# USB-C_Power_Supply.net
KiCad netlist of a schematic drawn in Altium Designer
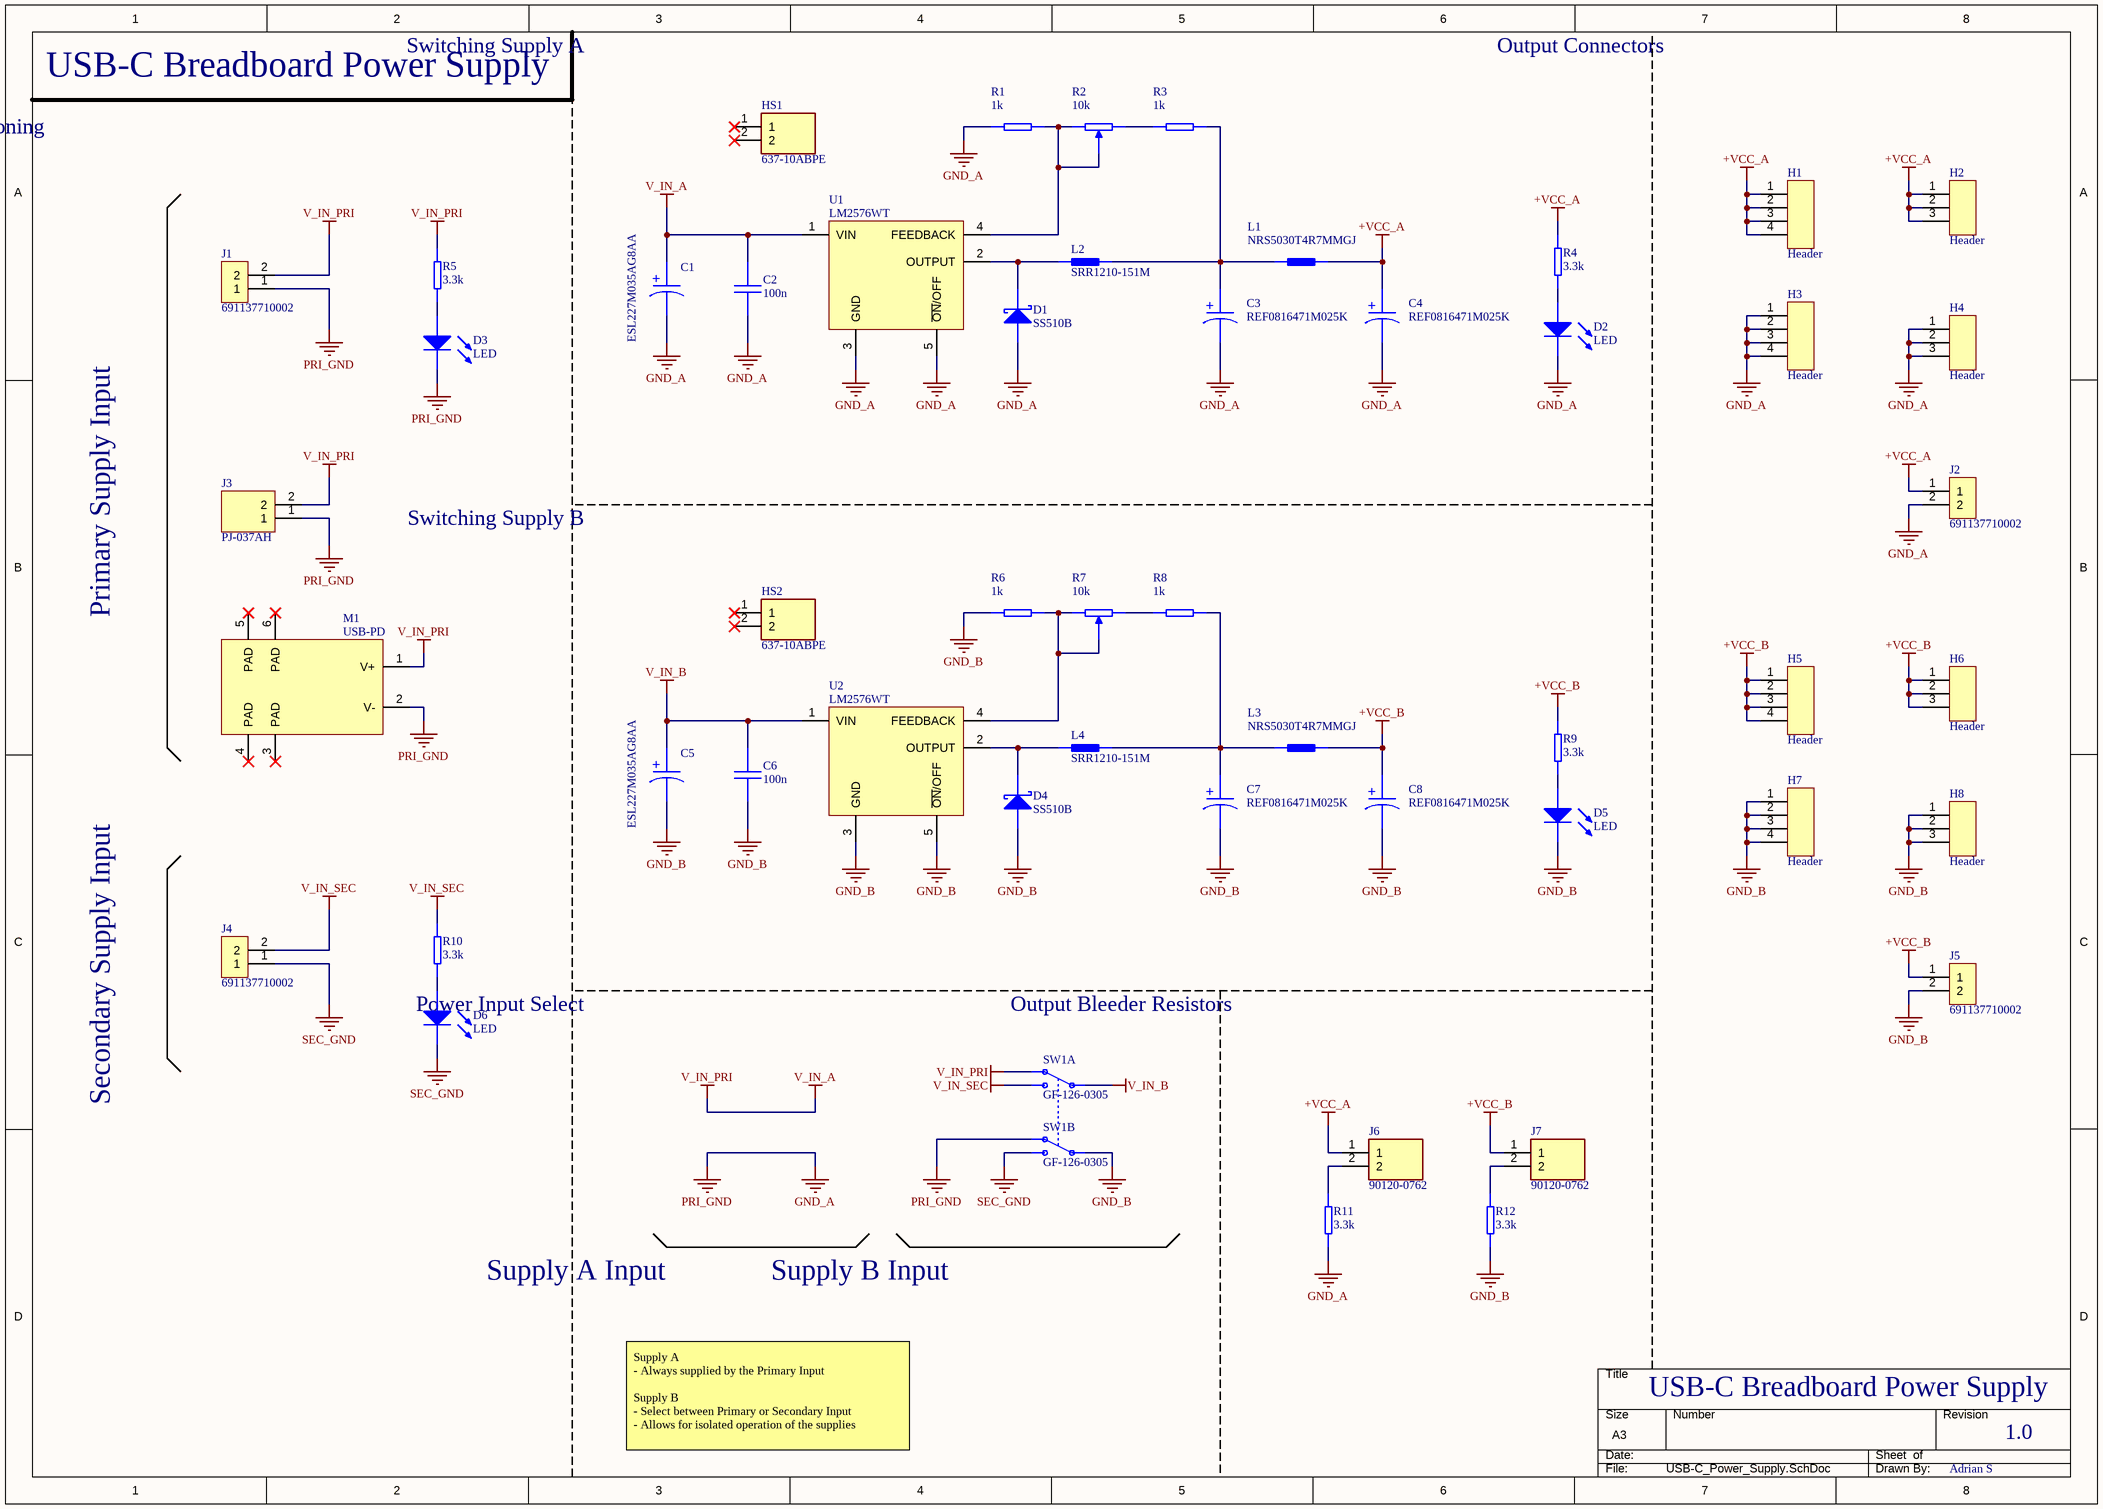
[diagram p0: USB-C_Power_Supply.SchDoc]

(export (version "E")
  (design (tool "Eeschema 10.0.6"))
  (components
    (comp (ref "C1")
      (value "ESL227M035AG8AA")
      (footprint "CAPTH8.00X18.00-3.50")
      (description "Capacitor Polarised")
      (fields (field (name "MOUSER PART NUMBER") "80-ESL227M035AG8AA"))
      (libsource (lib "TD") (part "ESL227M035AG8AA"))
    )
    (comp (ref "C2")
      (value "100n")
      (footprint "CAP0805")
      (description "Non Polarized Capacitor")
      (libsource (lib "TD") (part "Capacitor - Non Polarized"))
    )
    (comp (ref "C3")
      (value "REF0816471M025K")
      (footprint "CAPTH8.00X16.00-3.50")
      (description "Capacitor Polarised")
      (fields (field (name "MOUSER PART NUMBER") "581-REF0816471M025K"))
      (libsource (lib "TD") (part "REF0816471M025K"))
    )
    (comp (ref "C4")
      (value "REF0816471M025K")
      (footprint "CAPTH8.00X16.00-3.50")
      (description "Capacitor Polarised")
      (fields (field (name "MOUSER PART NUMBER") "581-REF0816471M025K"))
      (libsource (lib "TD") (part "REF0816471M025K"))
    )
    (comp (ref "C5")
      (value "ESL227M035AG8AA")
      (footprint "CAPTH8.00X18.00-3.50")
      (description "Capacitor Polarised")
      (fields (field (name "MOUSER PART NUMBER") "80-ESL227M035AG8AA"))
      (libsource (lib "TD") (part "ESL227M035AG8AA"))
    )
    (comp (ref "C6")
      (value "100n")
      (footprint "CAP0805")
      (description "Non Polarized Capacitor")
      (libsource (lib "TD") (part "Capacitor - Non Polarized"))
    )
    (comp (ref "C7")
      (value "REF0816471M025K")
      (footprint "CAPTH8.00X16.00-3.50")
      (description "Capacitor Polarised")
      (fields (field (name "MOUSER PART NUMBER") "581-REF0816471M025K"))
      (libsource (lib "TD") (part "REF0816471M025K"))
    )
    (comp (ref "C8")
      (value "REF0816471M025K")
      (footprint "CAPTH8.00X16.00-3.50")
      (description "Capacitor Polarised")
      (fields (field (name "MOUSER PART NUMBER") "581-REF0816471M025K"))
      (libsource (lib "TD") (part "REF0816471M025K"))
    )
    (comp (ref "D1")
      (value "SS510B")
      (footprint "DO-214AC (SMA)")
      (description "Diode")
      (libsource (lib "TD") (part "SS510B"))
    )
    (comp (ref "D2")
      (value "LED")
      (footprint "LEDM2012X80N")
      (description "General Purpose LED")
      (libsource (lib "TD") (part "LED"))
    )
    (comp (ref "D3")
      (value "LED")
      (footprint "LEDM2012X80N")
      (description "General Purpose LED")
      (libsource (lib "TD") (part "LED"))
    )
    (comp (ref "D4")
      (value "SS510B")
      (footprint "DO-214AC (SMA)")
      (description "Diode")
      (libsource (lib "TD") (part "SS510B"))
    )
    (comp (ref "D5")
      (value "LED")
      (footprint "LEDM2012X80N")
      (description "General Purpose LED")
      (libsource (lib "TD") (part "LED"))
    )
    (comp (ref "D6")
      (value "LED")
      (footprint "LEDM2012X80N")
      (description "General Purpose LED")
      (libsource (lib "TD") (part "LED"))
    )
    (comp (ref "H1")
      (value "Header")
      (footprint "Header_1X4")
      (description "4-Pin Header")
      (libsource (lib "TD") (part "4-Pin Header"))
    )
    (comp (ref "H2")
      (value "Header")
      (footprint "Header_1X3")
      (description "3-Pin Header")
      (libsource (lib "TD") (part "3-Pin Header"))
    )
    (comp (ref "H3")
      (value "Header")
      (footprint "Header_1X4")
      (description "4-Pin Header")
      (libsource (lib "TD") (part "4-Pin Header"))
    )
    (comp (ref "H4")
      (value "Header")
      (footprint "Header_1X3")
      (description "3-Pin Header")
      (libsource (lib "TD") (part "3-Pin Header"))
    )
    (comp (ref "H5")
      (value "Header")
      (footprint "Header_1X4")
      (description "4-Pin Header")
      (libsource (lib "TD") (part "4-Pin Header"))
    )
    (comp (ref "H6")
      (value "Header")
      (footprint "Header_1X3")
      (description "3-Pin Header")
      (libsource (lib "TD") (part "3-Pin Header"))
    )
    (comp (ref "H7")
      (value "Header")
      (footprint "Header_1X4")
      (description "4-Pin Header")
      (libsource (lib "TD") (part "4-Pin Header"))
    )
    (comp (ref "H8")
      (value "Header")
      (footprint "Header_1X3")
      (description "3-Pin Header")
      (libsource (lib "TD") (part "3-Pin Header"))
    )
    (comp (ref "HS1")
      (value "637-10ABPE")
      (footprint "63710ABPE")
      (description "Undefined or Miscellaneous")
      (fields (field (name "MOUSER PART NUMBER") "567-637-10ABPE"))
      (libsource (lib "*") (part "637-10ABPE"))
    )
    (comp (ref "HS2")
      (value "637-10ABPE")
      (footprint "63710ABPE")
      (description "Undefined or Miscellaneous")
      (fields (field (name "MOUSER PART NUMBER") "567-637-10ABPE"))
      (libsource (lib "*") (part "637-10ABPE"))
    )
    (comp (ref "J1")
      (value "691137710002")
      (footprint "SHDR2W70P0X500_1X2_1000X750X1160P")
      (description "Connector")
      (fields (field (name "MOUSER PART NUMBER") "710-691137710002"))
      (libsource (lib "") (part "691137710002_1"))
    )
    (comp (ref "J2")
      (value "691137710002")
      (footprint "SHDR2W70P0X500_1X2_1000X750X1160P")
      (description "Connector")
      (fields (field (name "MOUSER PART NUMBER") "710-691137710002"))
      (libsource (lib "TD") (part "691137710002"))
    )
    (comp (ref "J3")
      (value "PJ-037AH")
      (footprint "PJ037AH")
      (description "Connector")
      (fields (field (name "MOUSER PART NUMBER") "490-PJ-037AH"))
      (libsource (lib "TD") (part "PJ-037AH"))
    )
    (comp (ref "J4")
      (value "691137710002")
      (footprint "SHDR2W70P0X500_1X2_1000X750X1160P")
      (description "Connector")
      (fields (field (name "MOUSER PART NUMBER") "710-691137710002"))
      (libsource (lib "") (part "691137710002_1"))
    )
    (comp (ref "J5")
      (value "691137710002")
      (footprint "SHDR2W70P0X500_1X2_1000X750X1160P")
      (description "Connector")
      (fields (field (name "MOUSER PART NUMBER") "710-691137710002"))
      (libsource (lib "TD") (part "691137710002"))
    )
    (comp (ref "J6")
      (value "90120-0762")
      (footprint "Header_1X2")
      (description "Connector")
      (fields (field (name "MOUSER PART NUMBER") "538-90120-0762"))
      (libsource (lib "SamacSys") (part "90120-0762"))
    )
    (comp (ref "J7")
      (value "90120-0762")
      (footprint "Header_1X2")
      (description "Connector")
      (fields (field (name "MOUSER PART NUMBER") "538-90120-0762"))
      (libsource (lib "SamacSys") (part "90120-0762"))
    )
    (comp (ref "L1")
      (value "NRS5030T4R7MMGJ")
      (footprint "IND (4.9mmx4.9mm)")
      (description "Inductor")
      (fields (field (name "MOUSER PART NUMBER") "963-NRS5030T4R7MMGJ"))
      (libsource (lib "TD") (part "NRS5030T4R7MMGJ"))
    )
    (comp (ref "L2")
      (value "SRR1210-151M")
      (footprint "INDPM120120X1000N-D")
      (description "Inductor")
      (fields (field (name "MOUSER PART NUMBER") "652-SRR1210-151M"))
      (libsource (lib "TD") (part "SRR1210-151M"))
    )
    (comp (ref "L3")
      (value "NRS5030T4R7MMGJ")
      (footprint "IND (4.9mmx4.9mm)")
      (description "Inductor")
      (fields (field (name "MOUSER PART NUMBER") "963-NRS5030T4R7MMGJ"))
      (libsource (lib "TD") (part "NRS5030T4R7MMGJ"))
    )
    (comp (ref "L4")
      (value "SRR1210-151M")
      (footprint "INDPM120120X1000N-D")
      (description "Inductor")
      (fields (field (name "MOUSER PART NUMBER") "652-SRR1210-151M"))
      (libsource (lib "TD") (part "SRR1210-151M"))
    )
    (comp (ref "M1")
      (value "USB-PD")
      (footprint "USB_C-PD")
      (libsource (lib "IEEE_Workshop_SCH") (part "USB-PD"))
    )
    (comp (ref "R1")
      (value "1k")
      (footprint "RESC0805")
      (description "Resistor")
      (libsource (lib "TD") (part "Resistor"))
    )
    (comp (ref "R2")
      (value "10k")
      (footprint "3339P1103LF - Modified")
      (description "Potentionmeter")
      (libsource (lib "TD") (part "Potentiometer"))
    )
    (comp (ref "R3")
      (value "1k")
      (footprint "RESC0805")
      (description "Resistor")
      (libsource (lib "TD") (part "Resistor"))
    )
    (comp (ref "R4")
      (value "3.3k")
      (footprint "RESC0805")
      (description "Resistor")
      (libsource (lib "TD") (part "Resistor"))
    )
    (comp (ref "R5")
      (value "3.3k")
      (footprint "RESC0805")
      (description "Resistor")
      (libsource (lib "TD") (part "Resistor"))
    )
    (comp (ref "R6")
      (value "1k")
      (footprint "RESC0805")
      (description "Resistor")
      (libsource (lib "TD") (part "Resistor"))
    )
    (comp (ref "R7")
      (value "10k")
      (footprint "3339P1103LF - Modified")
      (description "Potentionmeter")
      (libsource (lib "TD") (part "Potentiometer"))
    )
    (comp (ref "R8")
      (value "1k")
      (footprint "RESC0805")
      (description "Resistor")
      (libsource (lib "TD") (part "Resistor"))
    )
    (comp (ref "R9")
      (value "3.3k")
      (footprint "RESC0805")
      (description "Resistor")
      (libsource (lib "TD") (part "Resistor"))
    )
    (comp (ref "R10")
      (value "3.3k")
      (footprint "RESC0805")
      (description "Resistor")
      (libsource (lib "TD") (part "Resistor"))
    )
    (comp (ref "R11")
      (value "3.3k")
      (footprint "RESC0805")
      (description "Resistor")
      (libsource (lib "TD") (part "Resistor"))
    )
    (comp (ref "R12")
      (value "3.3k")
      (footprint "RESC0805")
      (description "Resistor")
      (libsource (lib "TD") (part "Resistor"))
    )
    (comp (ref "SW1")
      (value "GF-126-0305")
      (footprint "GF1260305")
      (description "DPDT Slide Switch")
      (libsource (lib "TD") (part "GF-126-0305"))
    )
    (comp (ref "U1")
      (value "LM2576WT")
      (footprint "TO-220-5")
      (description "Integrated Circuit")
      (fields
        (field (name "MANUFACTURER_PART_NUMBER") "LM2576WU-TR")
        (field (name "MOUSER PART NUMBER") "998-LM2576WT")
      )
      (libsource (lib "TD") (part "LM2576WT"))
    )
    (comp (ref "U2")
      (value "LM2576WT")
      (footprint "TO-220-5")
      (description "Integrated Circuit")
      (fields
        (field (name "MANUFACTURER_PART_NUMBER") "LM2576WU-TR")
        (field (name "MOUSER PART NUMBER") "998-LM2576WT")
      )
      (libsource (lib "TD") (part "LM2576WT"))
    )
  )
  (nets
    (net (code "1") (name "+VCC_A") (class "Default")
      (node (ref "C4") (pin "1") (pintype "passive"))
      (node (ref "H1") (pin "1") (pintype "passive"))
      (node (ref "H1") (pin "2") (pintype "passive"))
      (node (ref "H1") (pin "3") (pintype "passive"))
      (node (ref "H1") (pin "4") (pintype "passive"))
      (node (ref "H2") (pin "1") (pintype "passive"))
      (node (ref "H2") (pin "2") (pintype "passive"))
      (node (ref "H2") (pin "3") (pintype "passive"))
      (node (ref "J2") (pin "1") (pinfunction "1_1") (pintype "passive"))
      (node (ref "J6") (pin "1") (pinfunction "1_1") (pintype "passive"))
      (node (ref "L1") (pin "2") (pintype "passive"))
      (node (ref "R4") (pin "1") (pintype "passive"))
    )
    (net (code "2") (name "+VCC_B") (class "Default")
      (node (ref "C8") (pin "1") (pintype "passive"))
      (node (ref "H5") (pin "1") (pintype "passive"))
      (node (ref "H5") (pin "2") (pintype "passive"))
      (node (ref "H5") (pin "3") (pintype "passive"))
      (node (ref "H5") (pin "4") (pintype "passive"))
      (node (ref "H6") (pin "1") (pintype "passive"))
      (node (ref "H6") (pin "2") (pintype "passive"))
      (node (ref "H6") (pin "3") (pintype "passive"))
      (node (ref "J5") (pin "1") (pinfunction "1_1") (pintype "passive"))
      (node (ref "J7") (pin "1") (pinfunction "1_1") (pintype "passive"))
      (node (ref "L3") (pin "2") (pintype "passive"))
      (node (ref "R9") (pin "1") (pintype "passive"))
    )
    (net (code "3") (name "GND_A") (class "Default")
      (node (ref "C1") (pin "2") (pintype "passive"))
      (node (ref "C2") (pin "2") (pintype "passive"))
      (node (ref "C3") (pin "2") (pintype "passive"))
      (node (ref "C4") (pin "2") (pintype "passive"))
      (node (ref "D1") (pin "2") (pinfunction "A_2") (pintype "passive"))
      (node (ref "D2") (pin "1") (pinfunction "K_1") (pintype "passive"))
      (node (ref "D3") (pin "1") (pinfunction "K_1") (pintype "passive"))
      (node (ref "H3") (pin "1") (pintype "passive"))
      (node (ref "H3") (pin "2") (pintype "passive"))
      (node (ref "H3") (pin "3") (pintype "passive"))
      (node (ref "H3") (pin "4") (pintype "passive"))
      (node (ref "H4") (pin "1") (pintype "passive"))
      (node (ref "H4") (pin "2") (pintype "passive"))
      (node (ref "H4") (pin "3") (pintype "passive"))
      (node (ref "J1") (pin "1") (pinfunction "1_1") (pintype "passive"))
      (node (ref "J2") (pin "2") (pinfunction "2_2") (pintype "passive"))
      (node (ref "J3") (pin "1") (pinfunction "1_1") (pintype "passive"))
      (node (ref "M1") (pin "2") (pinfunction "V-_2") (pintype "passive"))
      (node (ref "R1") (pin "2") (pintype "passive"))
      (node (ref "R11") (pin "2") (pintype "passive"))
      (node (ref "SW1") (pin "6") (pintype "passive"))
      (node (ref "U1") (pin "3") (pinfunction "GND_3") (pintype "passive"))
      (node (ref "U1") (pin "5") (pinfunction "~{ON}/OFF_5") (pintype "passive"))
    )
    (net (code "4") (name "GND_B") (class "Default")
      (node (ref "C5") (pin "2") (pintype "passive"))
      (node (ref "C6") (pin "2") (pintype "passive"))
      (node (ref "C7") (pin "2") (pintype "passive"))
      (node (ref "C8") (pin "2") (pintype "passive"))
      (node (ref "D4") (pin "2") (pinfunction "A_2") (pintype "passive"))
      (node (ref "D5") (pin "1") (pinfunction "K_1") (pintype "passive"))
      (node (ref "H7") (pin "1") (pintype "passive"))
      (node (ref "H7") (pin "2") (pintype "passive"))
      (node (ref "H7") (pin "3") (pintype "passive"))
      (node (ref "H7") (pin "4") (pintype "passive"))
      (node (ref "H8") (pin "1") (pintype "passive"))
      (node (ref "H8") (pin "2") (pintype "passive"))
      (node (ref "H8") (pin "3") (pintype "passive"))
      (node (ref "J5") (pin "2") (pinfunction "2_2") (pintype "passive"))
      (node (ref "R12") (pin "2") (pintype "passive"))
      (node (ref "R6") (pin "2") (pintype "passive"))
      (node (ref "SW1") (pin "5") (pintype "passive"))
      (node (ref "U2") (pin "3") (pinfunction "GND_3") (pintype "passive"))
      (node (ref "U2") (pin "5") (pinfunction "~{ON}/OFF_5") (pintype "passive"))
    )
    (net (code "5") (name "Net-(C3-Pad1)") (class "Default")
      (node (ref "C3") (pin "1") (pintype "passive"))
      (node (ref "L1") (pin "1") (pintype "passive"))
      (node (ref "L2") (pin "2") (pintype "passive"))
      (node (ref "R3") (pin "1") (pintype "passive"))
    )
    (net (code "6") (name "Net-(C7-Pad1)") (class "Default")
      (node (ref "C7") (pin "1") (pintype "passive"))
      (node (ref "L3") (pin "1") (pintype "passive"))
      (node (ref "L4") (pin "2") (pintype "passive"))
      (node (ref "R8") (pin "1") (pintype "passive"))
    )
    (net (code "7") (name "Net-(D1-K)") (class "Default")
      (node (ref "D1") (pin "1") (pinfunction "K_1") (pintype "passive"))
      (node (ref "L2") (pin "1") (pintype "passive"))
      (node (ref "U1") (pin "2") (pinfunction "OUTPUT_2") (pintype "passive"))
    )
    (net (code "8") (name "Net-(D2-A)") (class "Default")
      (node (ref "D2") (pin "2") (pinfunction "A_2") (pintype "passive"))
      (node (ref "R4") (pin "2") (pintype "passive"))
    )
    (net (code "9") (name "Net-(D3-A)") (class "Default")
      (node (ref "D3") (pin "2") (pinfunction "A_2") (pintype "passive"))
      (node (ref "R5") (pin "2") (pintype "passive"))
    )
    (net (code "10") (name "Net-(D4-K)") (class "Default")
      (node (ref "D4") (pin "1") (pinfunction "K_1") (pintype "passive"))
      (node (ref "L4") (pin "1") (pintype "passive"))
      (node (ref "U2") (pin "2") (pinfunction "OUTPUT_2") (pintype "passive"))
    )
    (net (code "11") (name "Net-(D5-A)") (class "Default")
      (node (ref "D5") (pin "2") (pinfunction "A_2") (pintype "passive"))
      (node (ref "R9") (pin "2") (pintype "passive"))
    )
    (net (code "12") (name "Net-(D6-A)") (class "Default")
      (node (ref "D6") (pin "2") (pinfunction "A_2") (pintype "passive"))
      (node (ref "R10") (pin "2") (pintype "passive"))
    )
    (net (code "13") (name "Net-(J6-Pad2)") (class "Default")
      (node (ref "J6") (pin "2") (pinfunction "2_2") (pintype "passive"))
      (node (ref "R11") (pin "1") (pintype "passive"))
    )
    (net (code "14") (name "Net-(J7-Pad2)") (class "Default")
      (node (ref "J7") (pin "2") (pinfunction "2_2") (pintype "passive"))
      (node (ref "R12") (pin "1") (pintype "passive"))
    )
    (net (code "15") (name "Net-(R2-Pad1)") (class "Default")
      (node (ref "R2") (pin "1") (pintype "passive"))
      (node (ref "R3") (pin "2") (pintype "passive"))
    )
    (net (code "16") (name "Net-(R7-Pad1)") (class "Default")
      (node (ref "R7") (pin "1") (pintype "passive"))
      (node (ref "R8") (pin "2") (pintype "passive"))
    )
    (net (code "17") (name "Net-(U1-FEEDBACK)") (class "Default")
      (node (ref "R1") (pin "1") (pintype "passive"))
      (node (ref "R2") (pin "2") (pintype "passive"))
      (node (ref "R2") (pin "3") (pintype "passive"))
      (node (ref "U1") (pin "4") (pinfunction "FEEDBACK_4") (pintype "passive"))
    )
    (net (code "18") (name "Net-(U2-FEEDBACK)") (class "Default")
      (node (ref "R6") (pin "1") (pintype "passive"))
      (node (ref "R7") (pin "2") (pintype "passive"))
      (node (ref "R7") (pin "3") (pintype "passive"))
      (node (ref "U2") (pin "4") (pinfunction "FEEDBACK_4") (pintype "passive"))
    )
    (net (code "19") (name "SEC_GND") (class "Default")
      (node (ref "D6") (pin "1") (pinfunction "K_1") (pintype "passive"))
      (node (ref "J4") (pin "1") (pinfunction "1_1") (pintype "passive"))
      (node (ref "SW1") (pin "4") (pintype "passive"))
    )
    (net (code "20") (name "V_IN_A") (class "Default")
      (node (ref "C1") (pin "1") (pintype "passive"))
      (node (ref "C2") (pin "1") (pintype "passive"))
      (node (ref "J1") (pin "2") (pinfunction "2_2") (pintype "passive"))
      (node (ref "J3") (pin "2") (pinfunction "2_2") (pintype "passive"))
      (node (ref "M1") (pin "1") (pinfunction "V+_1") (pintype "passive"))
      (node (ref "R5") (pin "1") (pintype "passive"))
      (node (ref "SW1") (pin "1") (pintype "passive"))
      (node (ref "U1") (pin "1") (pinfunction "VIN_1") (pintype "passive"))
    )
    (net (code "21") (name "V_IN_B") (class "Default")
      (node (ref "C5") (pin "1") (pintype "passive"))
      (node (ref "C6") (pin "1") (pintype "passive"))
      (node (ref "SW1") (pin "2") (pintype "passive"))
      (node (ref "U2") (pin "1") (pinfunction "VIN_1") (pintype "passive"))
    )
    (net (code "22") (name "V_IN_SEC") (class "Default")
      (node (ref "J4") (pin "2") (pinfunction "2_2") (pintype "passive"))
      (node (ref "R10") (pin "1") (pintype "passive"))
      (node (ref "SW1") (pin "3") (pintype "passive"))
    )
    (net (code "23") (name "unconnected-(HS1-Pad1)") (class "Default")
      (node (ref "HS1") (pin "1") (pinfunction "1_1") (pintype "passive+no_connect"))
    )
    (net (code "24") (name "unconnected-(HS1-Pad2)") (class "Default")
      (node (ref "HS1") (pin "2") (pinfunction "2_2") (pintype "passive+no_connect"))
    )
    (net (code "25") (name "unconnected-(HS2-Pad1)") (class "Default")
      (node (ref "HS2") (pin "1") (pinfunction "1_1") (pintype "passive+no_connect"))
    )
    (net (code "26") (name "unconnected-(HS2-Pad2)") (class "Default")
      (node (ref "HS2") (pin "2") (pinfunction "2_2") (pintype "passive+no_connect"))
    )
    (net (code "27") (name "unconnected-(M1-PAD-Pad3)") (class "Default")
      (node (ref "M1") (pin "3") (pinfunction "PAD_3") (pintype "passive+no_connect"))
    )
    (net (code "28") (name "unconnected-(M1-PAD-Pad4)") (class "Default")
      (node (ref "M1") (pin "4") (pinfunction "PAD_4") (pintype "passive+no_connect"))
    )
    (net (code "29") (name "unconnected-(M1-PAD-Pad5)") (class "Default")
      (node (ref "M1") (pin "5") (pinfunction "PAD_5") (pintype "passive+no_connect"))
    )
    (net (code "30") (name "unconnected-(M1-PAD-Pad6)") (class "Default")
      (node (ref "M1") (pin "6") (pinfunction "PAD_6") (pintype "passive+no_connect"))
    )
  )
)
